# Schematic.net
KiCad netlist of a schematic drawn in Altium Designer
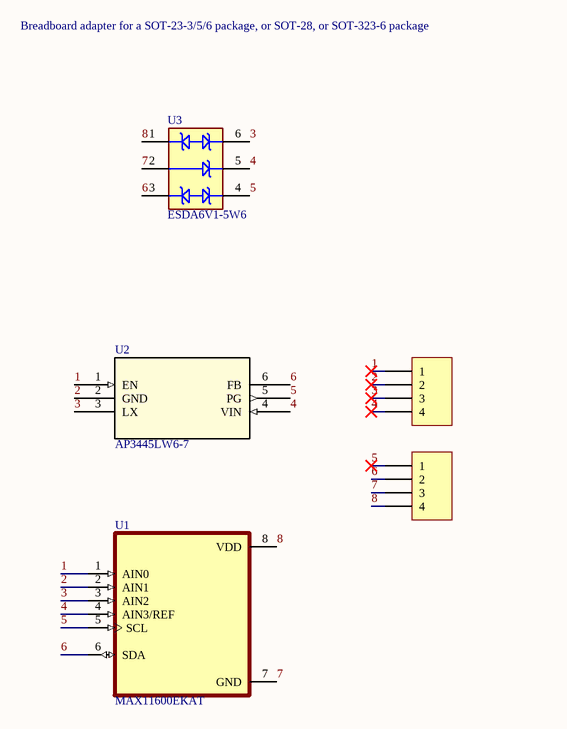
[diagram p0: Schematic.SchDoc]

(export (version "E")
  (design (tool "Eeschema 10.0.6"))
  (components
    (comp (ref "P1")
      (value "Header 4")
      (footprint "HDR1X4")
      (description "Header, 4-Pin")
      (fields (field (name "PUBLISHER") "Altium Limited"))
      (libsource (lib "Miscellaneous Connectors") (part "Header 4"))
    )
    (comp (ref "P2")
      (value "Header 4")
      (footprint "HDR1X4")
      (description "Header, 4-Pin")
      (fields (field (name "PUBLISHER") "Altium Limited"))
      (libsource (lib "Miscellaneous Connectors") (part "Header 4"))
    )
    (comp (ref "U1")
      (value "MAX11600EKAT")
      (footprint "SOT65P280X145-8N")
      (description "8 Bit Analog to Digital Converter 2, 4 Input 1 SAR SOT-23-8")
      (fields (field (name "MP") "MAX11600EKA+T") (field (name "MF") "Maxim Integrated"))
      (libsource (lib "MAX11600EKAT") (part "MAX11600EKAT"))
    )
    (comp (ref "U2")
      (value "AP3445LW6-7")
      (footprint "SOT26_AP3445_DIO")
      (description "No Description Available")
      (fields (field (name "COPYRIGHT") "Copyright (C) 2024 Ultra Librarian. All rights reserved."))
      (libsource (lib "AP3445LW6-7") (part "AP3445LW6-7"))
    )
    (comp (ref "U3")
      (value "ESDA6V1-5W6")
      (footprint "DIO_ESDA6V1-5W6")
      (description "- Clamp - Ipp Tvs Diode Surface Mount SOT-323-6L")
      (fields (field (name "MF") "STMicroelectronics"))
      (libsource (lib "ESDA6V1-5W6") (part "ESDA6V1-5W6"))
    )
  )
  (nets
    (net (code "1") (name "/1") (class "Default")
      (node (ref "P1") (pin "1") (pinfunction "1_1") (pintype "passive"))
      (node (ref "U1") (pin "1") (pinfunction "AIN0_1") (pintype "input"))
      (node (ref "U2") (pin "1") (pinfunction "EN_1") (pintype "input"))
    )
    (net (code "2") (name "/2") (class "Default")
      (node (ref "P1") (pin "2") (pinfunction "2_2") (pintype "passive"))
      (node (ref "U1") (pin "2") (pinfunction "AIN1_2") (pintype "input"))
      (node (ref "U2") (pin "2") (pinfunction "GND_2") (pintype "power_in"))
    )
    (net (code "3") (name "/3") (class "Default")
      (node (ref "P1") (pin "3") (pinfunction "3_3") (pintype "passive"))
      (node (ref "U1") (pin "3") (pinfunction "AIN2_3") (pintype "input"))
      (node (ref "U2") (pin "3") (pinfunction "LX_3") (pintype "passive"))
      (node (ref "U3") (pin "6") (pinfunction "6_6") (pintype "passive"))
    )
    (net (code "4") (name "/4") (class "Default")
      (node (ref "P1") (pin "4") (pinfunction "4_4") (pintype "passive"))
      (node (ref "U1") (pin "4") (pinfunction "AIN3/REF_4") (pintype "input"))
      (node (ref "U2") (pin "4") (pinfunction "VIN_4") (pintype "input"))
      (node (ref "U3") (pin "5") (pinfunction "5_5") (pintype "passive"))
    )
    (net (code "5") (name "/5") (class "Default")
      (node (ref "P2") (pin "1") (pinfunction "1_1") (pintype "passive"))
      (node (ref "U1") (pin "5") (pinfunction "SCL_5") (pintype "input"))
      (node (ref "U2") (pin "5") (pinfunction "PG_5") (pintype "output"))
      (node (ref "U3") (pin "4") (pinfunction "4_4") (pintype "passive"))
    )
    (net (code "6") (name "/6") (class "Default")
      (node (ref "P2") (pin "2") (pinfunction "2_2") (pintype "passive"))
      (node (ref "U1") (pin "6") (pinfunction "SDA_6") (pintype "bidirectional"))
      (node (ref "U2") (pin "6") (pinfunction "FB_6") (pintype "passive"))
      (node (ref "U3") (pin "3") (pinfunction "3_3") (pintype "passive"))
    )
    (net (code "7") (name "/7") (class "Default")
      (node (ref "P2") (pin "3") (pinfunction "3_3") (pintype "passive"))
      (node (ref "U1") (pin "7") (pinfunction "GND_7") (pintype "power_in"))
      (node (ref "U3") (pin "2") (pinfunction "2_2") (pintype "passive"))
    )
    (net (code "8") (name "/8") (class "Default")
      (node (ref "P2") (pin "4") (pinfunction "4_4") (pintype "passive"))
      (node (ref "U1") (pin "8") (pinfunction "VDD_8") (pintype "power_in"))
      (node (ref "U3") (pin "1") (pinfunction "1_1") (pintype "passive"))
    )
  )
)
